# Submarine_Control.net
KiCad netlist of a schematic drawn in Altium Designer
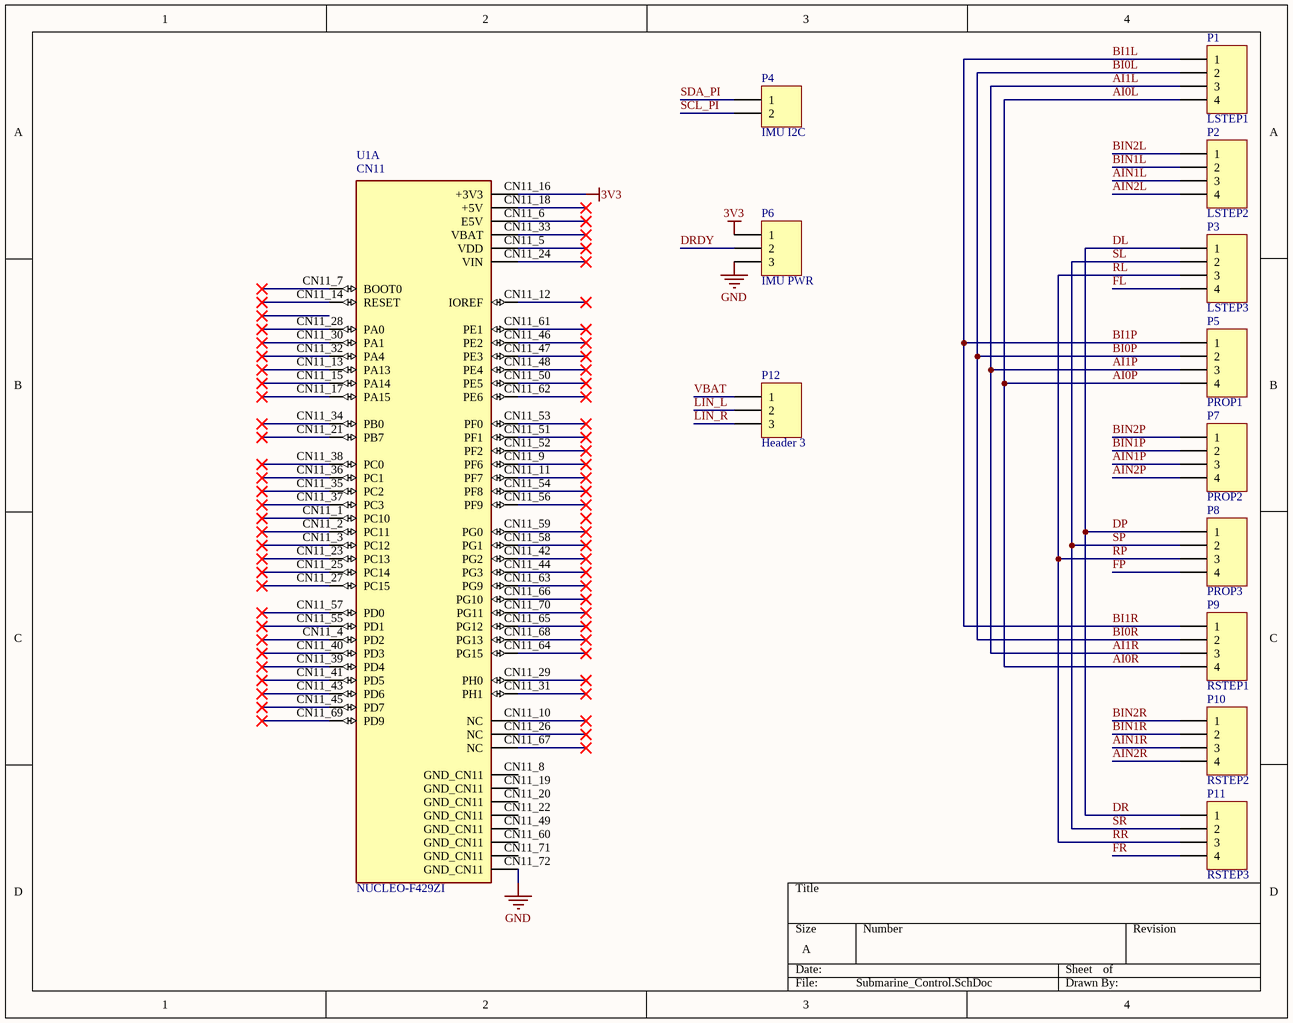
[diagram p0: Submarine_Control.SchDoc]

(export (version "E")
  (design (tool "Eeschema 10.0.6"))
  (components
    (comp (ref "P1")
      (value "LSTEP1")
      (footprint "HDR1X4")
      (description "Header, 4-Pin")
      (fields (field (name "PUBLISHER") "Altium Limited"))
      (libsource (lib "Miscellaneous Connectors") (part "Header 4"))
    )
    (comp (ref "P2")
      (value "LSTEP2")
      (footprint "HDR1X4")
      (description "Header, 4-Pin")
      (fields (field (name "PUBLISHER") "Altium Limited"))
      (libsource (lib "Miscellaneous Connectors") (part "Header 4"))
    )
    (comp (ref "P3")
      (value "LSTEP3")
      (footprint "HDR1X4")
      (description "Header, 4-Pin")
      (fields (field (name "PUBLISHER") "Altium Limited"))
      (libsource (lib "Miscellaneous Connectors") (part "Header 4"))
    )
    (comp (ref "P4")
      (value "IMU I2C")
      (footprint "HDR1X2")
      (description "Header, 2-Pin")
      (fields (field (name "PUBLISHER") "Altium Limited"))
      (libsource (lib "Miscellaneous Connectors") (part "Header 2"))
    )
    (comp (ref "P5")
      (value "PROP1")
      (footprint "HDR1X4")
      (description "Header, 4-Pin")
      (fields (field (name "PUBLISHER") "Altium Limited"))
      (libsource (lib "Miscellaneous Connectors") (part "Header 4"))
    )
    (comp (ref "P6")
      (value "IMU PWR")
      (footprint "HDR1X3")
      (description "Header, 3-Pin")
      (fields (field (name "PUBLISHER") "Altium Limited"))
      (libsource (lib "Miscellaneous Connectors") (part "Header 3"))
    )
    (comp (ref "P7")
      (value "PROP2")
      (footprint "HDR1X4")
      (description "Header, 4-Pin")
      (fields (field (name "PUBLISHER") "Altium Limited"))
      (libsource (lib "Miscellaneous Connectors") (part "Header 4"))
    )
    (comp (ref "P8")
      (value "PROP3")
      (footprint "HDR1X4")
      (description "Header, 4-Pin")
      (fields (field (name "PUBLISHER") "Altium Limited"))
      (libsource (lib "Miscellaneous Connectors") (part "Header 4"))
    )
    (comp (ref "P9")
      (value "RSTEP1")
      (footprint "HDR1X4")
      (description "Header, 4-Pin")
      (fields (field (name "PUBLISHER") "Altium Limited"))
      (libsource (lib "Miscellaneous Connectors") (part "Header 4"))
    )
    (comp (ref "P10")
      (value "RSTEP2")
      (footprint "HDR1X4")
      (description "Header, 4-Pin")
      (fields (field (name "PUBLISHER") "Altium Limited"))
      (libsource (lib "Miscellaneous Connectors") (part "Header 4"))
    )
    (comp (ref "P11")
      (value "RSTEP3")
      (footprint "HDR1X4")
      (description "Header, 4-Pin")
      (fields (field (name "PUBLISHER") "Altium Limited"))
      (libsource (lib "Miscellaneous Connectors") (part "Header 4"))
    )
    (comp (ref "P12")
      (value "Header 3")
      (footprint "HDR1X3")
      (description "Header, 3-Pin")
      (fields (field (name "PUBLISHER") "Altium Limited"))
      (libsource (lib "Miscellaneous Connectors") (part "Header 3"))
    )
    (comp (ref "U1")
      (value "NUCLEO-F429ZI")
      (footprint "MODULE_NUCLEO-F429ZI")
      (fields (field (name "MF") "STMicroelectronics"))
      (libsource (lib "NUCLEO-F429ZI") (part "NUCLEO-F429ZI"))
    )
  )
  (nets
    (net (code "1") (name "/AI0L") (class "Default")
      (node (ref "P1") (pin "4") (pinfunction "4_4") (pintype "passive"))
      (node (ref "P5") (pin "4") (pinfunction "4_4") (pintype "passive"))
      (node (ref "P9") (pin "4") (pinfunction "4_4") (pintype "passive"))
    )
    (net (code "2") (name "/AI1L") (class "Default")
      (node (ref "P1") (pin "3") (pinfunction "3_3") (pintype "passive"))
      (node (ref "P5") (pin "3") (pinfunction "3_3") (pintype "passive"))
      (node (ref "P9") (pin "3") (pinfunction "3_3") (pintype "passive"))
    )
    (net (code "3") (name "/AIN1L") (class "Default")
      (node (ref "P2") (pin "3") (pinfunction "3_3") (pintype "passive"))
    )
    (net (code "4") (name "/AIN1P") (class "Default")
      (node (ref "P7") (pin "3") (pinfunction "3_3") (pintype "passive"))
    )
    (net (code "5") (name "/AIN1R") (class "Default")
      (node (ref "P10") (pin "3") (pinfunction "3_3") (pintype "passive"))
    )
    (net (code "6") (name "/AIN2L") (class "Default")
      (node (ref "P2") (pin "4") (pinfunction "4_4") (pintype "passive"))
    )
    (net (code "7") (name "/AIN2P") (class "Default")
      (node (ref "P7") (pin "4") (pinfunction "4_4") (pintype "passive"))
    )
    (net (code "8") (name "/AIN2R") (class "Default")
      (node (ref "P10") (pin "4") (pinfunction "4_4") (pintype "passive"))
    )
    (net (code "9") (name "/BI0L") (class "Default")
      (node (ref "P1") (pin "2") (pinfunction "2_2") (pintype "passive"))
      (node (ref "P5") (pin "2") (pinfunction "2_2") (pintype "passive"))
      (node (ref "P9") (pin "2") (pinfunction "2_2") (pintype "passive"))
    )
    (net (code "10") (name "/BI1L") (class "Default")
      (node (ref "P1") (pin "1") (pinfunction "1_1") (pintype "passive"))
      (node (ref "P5") (pin "1") (pinfunction "1_1") (pintype "passive"))
      (node (ref "P9") (pin "1") (pinfunction "1_1") (pintype "passive"))
    )
    (net (code "11") (name "/BIN1L") (class "Default")
      (node (ref "P2") (pin "2") (pinfunction "2_2") (pintype "passive"))
    )
    (net (code "12") (name "/BIN1P") (class "Default")
      (node (ref "P7") (pin "2") (pinfunction "2_2") (pintype "passive"))
    )
    (net (code "13") (name "/BIN1R") (class "Default")
      (node (ref "P10") (pin "2") (pinfunction "2_2") (pintype "passive"))
    )
    (net (code "14") (name "/BIN2L") (class "Default")
      (node (ref "P2") (pin "1") (pinfunction "1_1") (pintype "passive"))
    )
    (net (code "15") (name "/BIN2P") (class "Default")
      (node (ref "P7") (pin "1") (pinfunction "1_1") (pintype "passive"))
    )
    (net (code "16") (name "/BIN2R") (class "Default")
      (node (ref "P10") (pin "1") (pinfunction "1_1") (pintype "passive"))
    )
    (net (code "17") (name "/DL") (class "Default")
      (node (ref "P11") (pin "1") (pinfunction "1_1") (pintype "passive"))
      (node (ref "P3") (pin "1") (pinfunction "1_1") (pintype "passive"))
      (node (ref "P8") (pin "1") (pinfunction "1_1") (pintype "passive"))
    )
    (net (code "18") (name "/DRDY") (class "Default")
      (node (ref "P6") (pin "2") (pinfunction "2_2") (pintype "passive"))
    )
    (net (code "19") (name "/FL") (class "Default")
      (node (ref "P3") (pin "4") (pinfunction "4_4") (pintype "passive"))
    )
    (net (code "20") (name "/FP") (class "Default")
      (node (ref "P8") (pin "4") (pinfunction "4_4") (pintype "passive"))
    )
    (net (code "21") (name "/FR") (class "Default")
      (node (ref "P11") (pin "4") (pinfunction "4_4") (pintype "passive"))
    )
    (net (code "22") (name "/LIN_L") (class "Default")
      (node (ref "P12") (pin "2") (pinfunction "2_2") (pintype "passive"))
    )
    (net (code "23") (name "/LIN_R") (class "Default")
      (node (ref "P12") (pin "3") (pinfunction "3_3") (pintype "passive"))
    )
    (net (code "24") (name "/RL") (class "Default")
      (node (ref "P11") (pin "3") (pinfunction "3_3") (pintype "passive"))
      (node (ref "P3") (pin "3") (pinfunction "3_3") (pintype "passive"))
      (node (ref "P8") (pin "3") (pinfunction "3_3") (pintype "passive"))
    )
    (net (code "25") (name "/SCL_PI") (class "Default")
      (node (ref "P4") (pin "2") (pinfunction "2_2") (pintype "passive"))
    )
    (net (code "26") (name "/SDA_PI") (class "Default")
      (node (ref "P4") (pin "1") (pinfunction "1_1") (pintype "passive"))
    )
    (net (code "27") (name "/SL") (class "Default")
      (node (ref "P11") (pin "2") (pinfunction "2_2") (pintype "passive"))
      (node (ref "P3") (pin "2") (pinfunction "2_2") (pintype "passive"))
      (node (ref "P8") (pin "2") (pinfunction "2_2") (pintype "passive"))
    )
    (net (code "28") (name "/VBAT") (class "Default")
      (node (ref "P12") (pin "1") (pinfunction "1_1") (pintype "passive"))
    )
    (net (code "29") (name "3V3") (class "Default")
      (node (ref "P6") (pin "1") (pinfunction "1_1") (pintype "passive"))
      (node (ref "U1") (pin "CN11_16") (pinfunction "+3V3_CN11_16") (pintype "power_in"))
    )
    (net (code "30") (name "GND") (class "Default")
      (node (ref "P6") (pin "3") (pinfunction "3_3") (pintype "passive"))
      (node (ref "U1") (pin "CN11_72") (pinfunction "GND_CN11_CN11_72") (pintype "power_in"))
    )
    (net (code "31") (name "unconnected-(U1A-+5V-PadCN11_18)") (class "Default")
      (node (ref "U1") (pin "CN11_18") (pinfunction "+5V_CN11_18") (pintype "power_in+no_connect"))
    )
    (net (code "32") (name "unconnected-(U1A-BOOT0-PadCN11_7)") (class "Default")
      (node (ref "U1") (pin "CN11_7") (pinfunction "BOOT0_CN11_7") (pintype "bidirectional+no_connect"))
    )
    (net (code "33") (name "unconnected-(U1A-E5V-PadCN11_6)") (class "Default")
      (node (ref "U1") (pin "CN11_6") (pinfunction "E5V_CN11_6") (pintype "power_in+no_connect"))
    )
    (net (code "34") (name "unconnected-(U1A-GND_CN11-PadCN11_8)") (class "Default")
      (node (ref "U1") (pin "CN11_8") (pinfunction "GND_CN11_CN11_8") (pintype "power_in"))
    )
    (net (code "35") (name "unconnected-(U1A-GND_CN11-PadCN11_19)") (class "Default")
      (node (ref "U1") (pin "CN11_19") (pinfunction "GND_CN11_CN11_19") (pintype "power_in"))
    )
    (net (code "36") (name "unconnected-(U1A-GND_CN11-PadCN11_20)") (class "Default")
      (node (ref "U1") (pin "CN11_20") (pinfunction "GND_CN11_CN11_20") (pintype "power_in"))
    )
    (net (code "37") (name "unconnected-(U1A-GND_CN11-PadCN11_22)") (class "Default")
      (node (ref "U1") (pin "CN11_22") (pinfunction "GND_CN11_CN11_22") (pintype "power_in"))
    )
    (net (code "38") (name "unconnected-(U1A-GND_CN11-PadCN11_49)") (class "Default")
      (node (ref "U1") (pin "CN11_49") (pinfunction "GND_CN11_CN11_49") (pintype "power_in"))
    )
    (net (code "39") (name "unconnected-(U1A-GND_CN11-PadCN11_60)") (class "Default")
      (node (ref "U1") (pin "CN11_60") (pinfunction "GND_CN11_CN11_60") (pintype "power_in"))
    )
    (net (code "40") (name "unconnected-(U1A-GND_CN11-PadCN11_71)") (class "Default")
      (node (ref "U1") (pin "CN11_71") (pinfunction "GND_CN11_CN11_71") (pintype "power_in"))
    )
    (net (code "41") (name "unconnected-(U1A-IOREF-PadCN11_12)") (class "Default")
      (node (ref "U1") (pin "CN11_12") (pinfunction "IOREF_CN11_12") (pintype "bidirectional+no_connect"))
    )
    (net (code "42") (name "unconnected-(U1A-NC-PadCN11_10)") (class "Default")
      (node (ref "U1") (pin "CN11_10") (pinfunction "NC_CN11_10") (pintype "passive+no_connect"))
    )
    (net (code "43") (name "unconnected-(U1A-NC-PadCN11_26)") (class "Default")
      (node (ref "U1") (pin "CN11_26") (pinfunction "NC_CN11_26") (pintype "passive+no_connect"))
    )
    (net (code "44") (name "unconnected-(U1A-NC-PadCN11_67)") (class "Default")
      (node (ref "U1") (pin "CN11_67") (pinfunction "NC_CN11_67") (pintype "passive+no_connect"))
    )
    (net (code "45") (name "unconnected-(U1A-PA0-PadCN11_28)") (class "Default")
      (node (ref "U1") (pin "CN11_28") (pinfunction "PA0_CN11_28") (pintype "bidirectional+no_connect"))
    )
    (net (code "46") (name "unconnected-(U1A-PA1-PadCN11_30)") (class "Default")
      (node (ref "U1") (pin "CN11_30") (pinfunction "PA1_CN11_30") (pintype "bidirectional+no_connect"))
    )
    (net (code "47") (name "unconnected-(U1A-PA4-PadCN11_32)") (class "Default")
      (node (ref "U1") (pin "CN11_32") (pinfunction "PA4_CN11_32") (pintype "bidirectional+no_connect"))
    )
    (net (code "48") (name "unconnected-(U1A-PA13-PadCN11_13)") (class "Default")
      (node (ref "U1") (pin "CN11_13") (pinfunction "PA13_CN11_13") (pintype "bidirectional+no_connect"))
    )
    (net (code "49") (name "unconnected-(U1A-PA14-PadCN11_15)") (class "Default")
      (node (ref "U1") (pin "CN11_15") (pinfunction "PA14_CN11_15") (pintype "bidirectional+no_connect"))
    )
    (net (code "50") (name "unconnected-(U1A-PA15-PadCN11_17)") (class "Default")
      (node (ref "U1") (pin "CN11_17") (pinfunction "PA15_CN11_17") (pintype "bidirectional+no_connect"))
    )
    (net (code "51") (name "unconnected-(U1A-PB0-PadCN11_34)") (class "Default")
      (node (ref "U1") (pin "CN11_34") (pinfunction "PB0_CN11_34") (pintype "bidirectional+no_connect"))
    )
    (net (code "52") (name "unconnected-(U1A-PB7-PadCN11_21)") (class "Default")
      (node (ref "U1") (pin "CN11_21") (pinfunction "PB7_CN11_21") (pintype "bidirectional+no_connect"))
    )
    (net (code "53") (name "unconnected-(U1A-PC0-PadCN11_38)") (class "Default")
      (node (ref "U1") (pin "CN11_38") (pinfunction "PC0_CN11_38") (pintype "bidirectional+no_connect"))
    )
    (net (code "54") (name "unconnected-(U1A-PC1-PadCN11_36)") (class "Default")
      (node (ref "U1") (pin "CN11_36") (pinfunction "PC1_CN11_36") (pintype "bidirectional+no_connect"))
    )
    (net (code "55") (name "unconnected-(U1A-PC2-PadCN11_35)") (class "Default")
      (node (ref "U1") (pin "CN11_35") (pinfunction "PC2_CN11_35") (pintype "bidirectional+no_connect"))
    )
    (net (code "56") (name "unconnected-(U1A-PC3-PadCN11_37)") (class "Default")
      (node (ref "U1") (pin "CN11_37") (pinfunction "PC3_CN11_37") (pintype "bidirectional+no_connect"))
    )
    (net (code "57") (name "unconnected-(U1A-PC10-PadCN11_1)") (class "Default")
      (node (ref "U1") (pin "CN11_1") (pinfunction "PC10_CN11_1") (pintype "bidirectional+no_connect"))
    )
    (net (code "58") (name "unconnected-(U1A-PC11-PadCN11_2)") (class "Default")
      (node (ref "U1") (pin "CN11_2") (pinfunction "PC11_CN11_2") (pintype "bidirectional+no_connect"))
    )
    (net (code "59") (name "unconnected-(U1A-PC12-PadCN11_3)") (class "Default")
      (node (ref "U1") (pin "CN11_3") (pinfunction "PC12_CN11_3") (pintype "bidirectional+no_connect"))
    )
    (net (code "60") (name "unconnected-(U1A-PC13-PadCN11_23)") (class "Default")
      (node (ref "U1") (pin "CN11_23") (pinfunction "PC13_CN11_23") (pintype "bidirectional+no_connect"))
    )
    (net (code "61") (name "unconnected-(U1A-PC14-PadCN11_25)") (class "Default")
      (node (ref "U1") (pin "CN11_25") (pinfunction "PC14_CN11_25") (pintype "bidirectional+no_connect"))
    )
    (net (code "62") (name "unconnected-(U1A-PC15-PadCN11_27)") (class "Default")
      (node (ref "U1") (pin "CN11_27") (pinfunction "PC15_CN11_27") (pintype "bidirectional+no_connect"))
    )
    (net (code "63") (name "unconnected-(U1A-PD0-PadCN11_57)") (class "Default")
      (node (ref "U1") (pin "CN11_57") (pinfunction "PD0_CN11_57") (pintype "bidirectional+no_connect"))
    )
    (net (code "64") (name "unconnected-(U1A-PD1-PadCN11_55)") (class "Default")
      (node (ref "U1") (pin "CN11_55") (pinfunction "PD1_CN11_55") (pintype "bidirectional+no_connect"))
    )
    (net (code "65") (name "unconnected-(U1A-PD2-PadCN11_4)") (class "Default")
      (node (ref "U1") (pin "CN11_4") (pinfunction "PD2_CN11_4") (pintype "bidirectional+no_connect"))
    )
    (net (code "66") (name "unconnected-(U1A-PD3-PadCN11_40)") (class "Default")
      (node (ref "U1") (pin "CN11_40") (pinfunction "PD3_CN11_40") (pintype "bidirectional+no_connect"))
    )
    (net (code "67") (name "unconnected-(U1A-PD4-PadCN11_39)") (class "Default")
      (node (ref "U1") (pin "CN11_39") (pinfunction "PD4_CN11_39") (pintype "bidirectional+no_connect"))
    )
    (net (code "68") (name "unconnected-(U1A-PD5-PadCN11_41)") (class "Default")
      (node (ref "U1") (pin "CN11_41") (pinfunction "PD5_CN11_41") (pintype "bidirectional+no_connect"))
    )
    (net (code "69") (name "unconnected-(U1A-PD6-PadCN11_43)") (class "Default")
      (node (ref "U1") (pin "CN11_43") (pinfunction "PD6_CN11_43") (pintype "bidirectional+no_connect"))
    )
    (net (code "70") (name "unconnected-(U1A-PD7-PadCN11_45)") (class "Default")
      (node (ref "U1") (pin "CN11_45") (pinfunction "PD7_CN11_45") (pintype "bidirectional+no_connect"))
    )
    (net (code "71") (name "unconnected-(U1A-PD9-PadCN11_69)") (class "Default")
      (node (ref "U1") (pin "CN11_69") (pinfunction "PD9_CN11_69") (pintype "bidirectional+no_connect"))
    )
    (net (code "72") (name "unconnected-(U1A-PE1-PadCN11_61)") (class "Default")
      (node (ref "U1") (pin "CN11_61") (pinfunction "PE1_CN11_61") (pintype "bidirectional+no_connect"))
    )
    (net (code "73") (name "unconnected-(U1A-PE2-PadCN11_46)") (class "Default")
      (node (ref "U1") (pin "CN11_46") (pinfunction "PE2_CN11_46") (pintype "bidirectional+no_connect"))
    )
    (net (code "74") (name "unconnected-(U1A-PE3-PadCN11_47)") (class "Default")
      (node (ref "U1") (pin "CN11_47") (pinfunction "PE3_CN11_47") (pintype "bidirectional+no_connect"))
    )
    (net (code "75") (name "unconnected-(U1A-PE4-PadCN11_48)") (class "Default")
      (node (ref "U1") (pin "CN11_48") (pinfunction "PE4_CN11_48") (pintype "bidirectional+no_connect"))
    )
    (net (code "76") (name "unconnected-(U1A-PE5-PadCN11_50)") (class "Default")
      (node (ref "U1") (pin "CN11_50") (pinfunction "PE5_CN11_50") (pintype "bidirectional+no_connect"))
    )
    (net (code "77") (name "unconnected-(U1A-PE6-PadCN11_62)") (class "Default")
      (node (ref "U1") (pin "CN11_62") (pinfunction "PE6_CN11_62") (pintype "bidirectional+no_connect"))
    )
    (net (code "78") (name "unconnected-(U1A-PF0-PadCN11_53)") (class "Default")
      (node (ref "U1") (pin "CN11_53") (pinfunction "PF0_CN11_53") (pintype "bidirectional+no_connect"))
    )
    (net (code "79") (name "unconnected-(U1A-PF1-PadCN11_51)") (class "Default")
      (node (ref "U1") (pin "CN11_51") (pinfunction "PF1_CN11_51") (pintype "bidirectional+no_connect"))
    )
    (net (code "80") (name "unconnected-(U1A-PF2-PadCN11_52)") (class "Default")
      (node (ref "U1") (pin "CN11_52") (pinfunction "PF2_CN11_52") (pintype "bidirectional+no_connect"))
    )
    (net (code "81") (name "unconnected-(U1A-PF6-PadCN11_9)") (class "Default")
      (node (ref "U1") (pin "CN11_9") (pinfunction "PF6_CN11_9") (pintype "bidirectional+no_connect"))
    )
    (net (code "82") (name "unconnected-(U1A-PF7-PadCN11_11)") (class "Default")
      (node (ref "U1") (pin "CN11_11") (pinfunction "PF7_CN11_11") (pintype "bidirectional+no_connect"))
    )
    (net (code "83") (name "unconnected-(U1A-PF8-PadCN11_54)") (class "Default")
      (node (ref "U1") (pin "CN11_54") (pinfunction "PF8_CN11_54") (pintype "bidirectional+no_connect"))
    )
    (net (code "84") (name "unconnected-(U1A-PF9-PadCN11_56)") (class "Default")
      (node (ref "U1") (pin "CN11_56") (pinfunction "PF9_CN11_56") (pintype "bidirectional+no_connect"))
    )
    (net (code "85") (name "unconnected-(U1A-PG0-PadCN11_59)") (class "Default")
      (node (ref "U1") (pin "CN11_59") (pinfunction "PG0_CN11_59") (pintype "bidirectional+no_connect"))
    )
    (net (code "86") (name "unconnected-(U1A-PG1-PadCN11_58)") (class "Default")
      (node (ref "U1") (pin "CN11_58") (pinfunction "PG1_CN11_58") (pintype "bidirectional+no_connect"))
    )
    (net (code "87") (name "unconnected-(U1A-PG2-PadCN11_42)") (class "Default")
      (node (ref "U1") (pin "CN11_42") (pinfunction "PG2_CN11_42") (pintype "bidirectional+no_connect"))
    )
    (net (code "88") (name "unconnected-(U1A-PG3-PadCN11_44)") (class "Default")
      (node (ref "U1") (pin "CN11_44") (pinfunction "PG3_CN11_44") (pintype "bidirectional+no_connect"))
    )
    (net (code "89") (name "unconnected-(U1A-PG9-PadCN11_63)") (class "Default")
      (node (ref "U1") (pin "CN11_63") (pinfunction "PG9_CN11_63") (pintype "bidirectional+no_connect"))
    )
    (net (code "90") (name "unconnected-(U1A-PG10-PadCN11_66)") (class "Default")
      (node (ref "U1") (pin "CN11_66") (pinfunction "PG10_CN11_66") (pintype "bidirectional+no_connect"))
    )
    (net (code "91") (name "unconnected-(U1A-PG11-PadCN11_70)") (class "Default")
      (node (ref "U1") (pin "CN11_70") (pinfunction "PG11_CN11_70") (pintype "bidirectional+no_connect"))
    )
    (net (code "92") (name "unconnected-(U1A-PG12-PadCN11_65)") (class "Default")
      (node (ref "U1") (pin "CN11_65") (pinfunction "PG12_CN11_65") (pintype "bidirectional+no_connect"))
    )
    (net (code "93") (name "unconnected-(U1A-PG13-PadCN11_68)") (class "Default")
      (node (ref "U1") (pin "CN11_68") (pinfunction "PG13_CN11_68") (pintype "bidirectional+no_connect"))
    )
    (net (code "94") (name "unconnected-(U1A-PG15-PadCN11_64)") (class "Default")
      (node (ref "U1") (pin "CN11_64") (pinfunction "PG15_CN11_64") (pintype "bidirectional+no_connect"))
    )
    (net (code "95") (name "unconnected-(U1A-PH0-PadCN11_29)") (class "Default")
      (node (ref "U1") (pin "CN11_29") (pinfunction "PH0_CN11_29") (pintype "bidirectional+no_connect"))
    )
    (net (code "96") (name "unconnected-(U1A-PH1-PadCN11_31)") (class "Default")
      (node (ref "U1") (pin "CN11_31") (pinfunction "PH1_CN11_31") (pintype "bidirectional+no_connect"))
    )
    (net (code "97") (name "unconnected-(U1A-RESET-PadCN11_14)") (class "Default")
      (node (ref "U1") (pin "CN11_14") (pinfunction "RESET_CN11_14") (pintype "bidirectional+no_connect"))
    )
    (net (code "98") (name "unconnected-(U1A-VBAT-PadCN11_33)") (class "Default")
      (node (ref "U1") (pin "CN11_33") (pinfunction "VBAT_CN11_33") (pintype "power_in+no_connect"))
    )
    (net (code "99") (name "unconnected-(U1A-VDD-PadCN11_5)") (class "Default")
      (node (ref "U1") (pin "CN11_5") (pinfunction "VDD_CN11_5") (pintype "power_in+no_connect"))
    )
    (net (code "100") (name "unconnected-(U1A-VIN-PadCN11_24)") (class "Default")
      (node (ref "U1") (pin "CN11_24") (pinfunction "VIN_CN11_24") (pintype "power_in+no_connect"))
    )
  )
)
